# microsmt_pnpboard_v17_sheet_2.net
KiCad netlist of a schematic drawn in Altium Designer
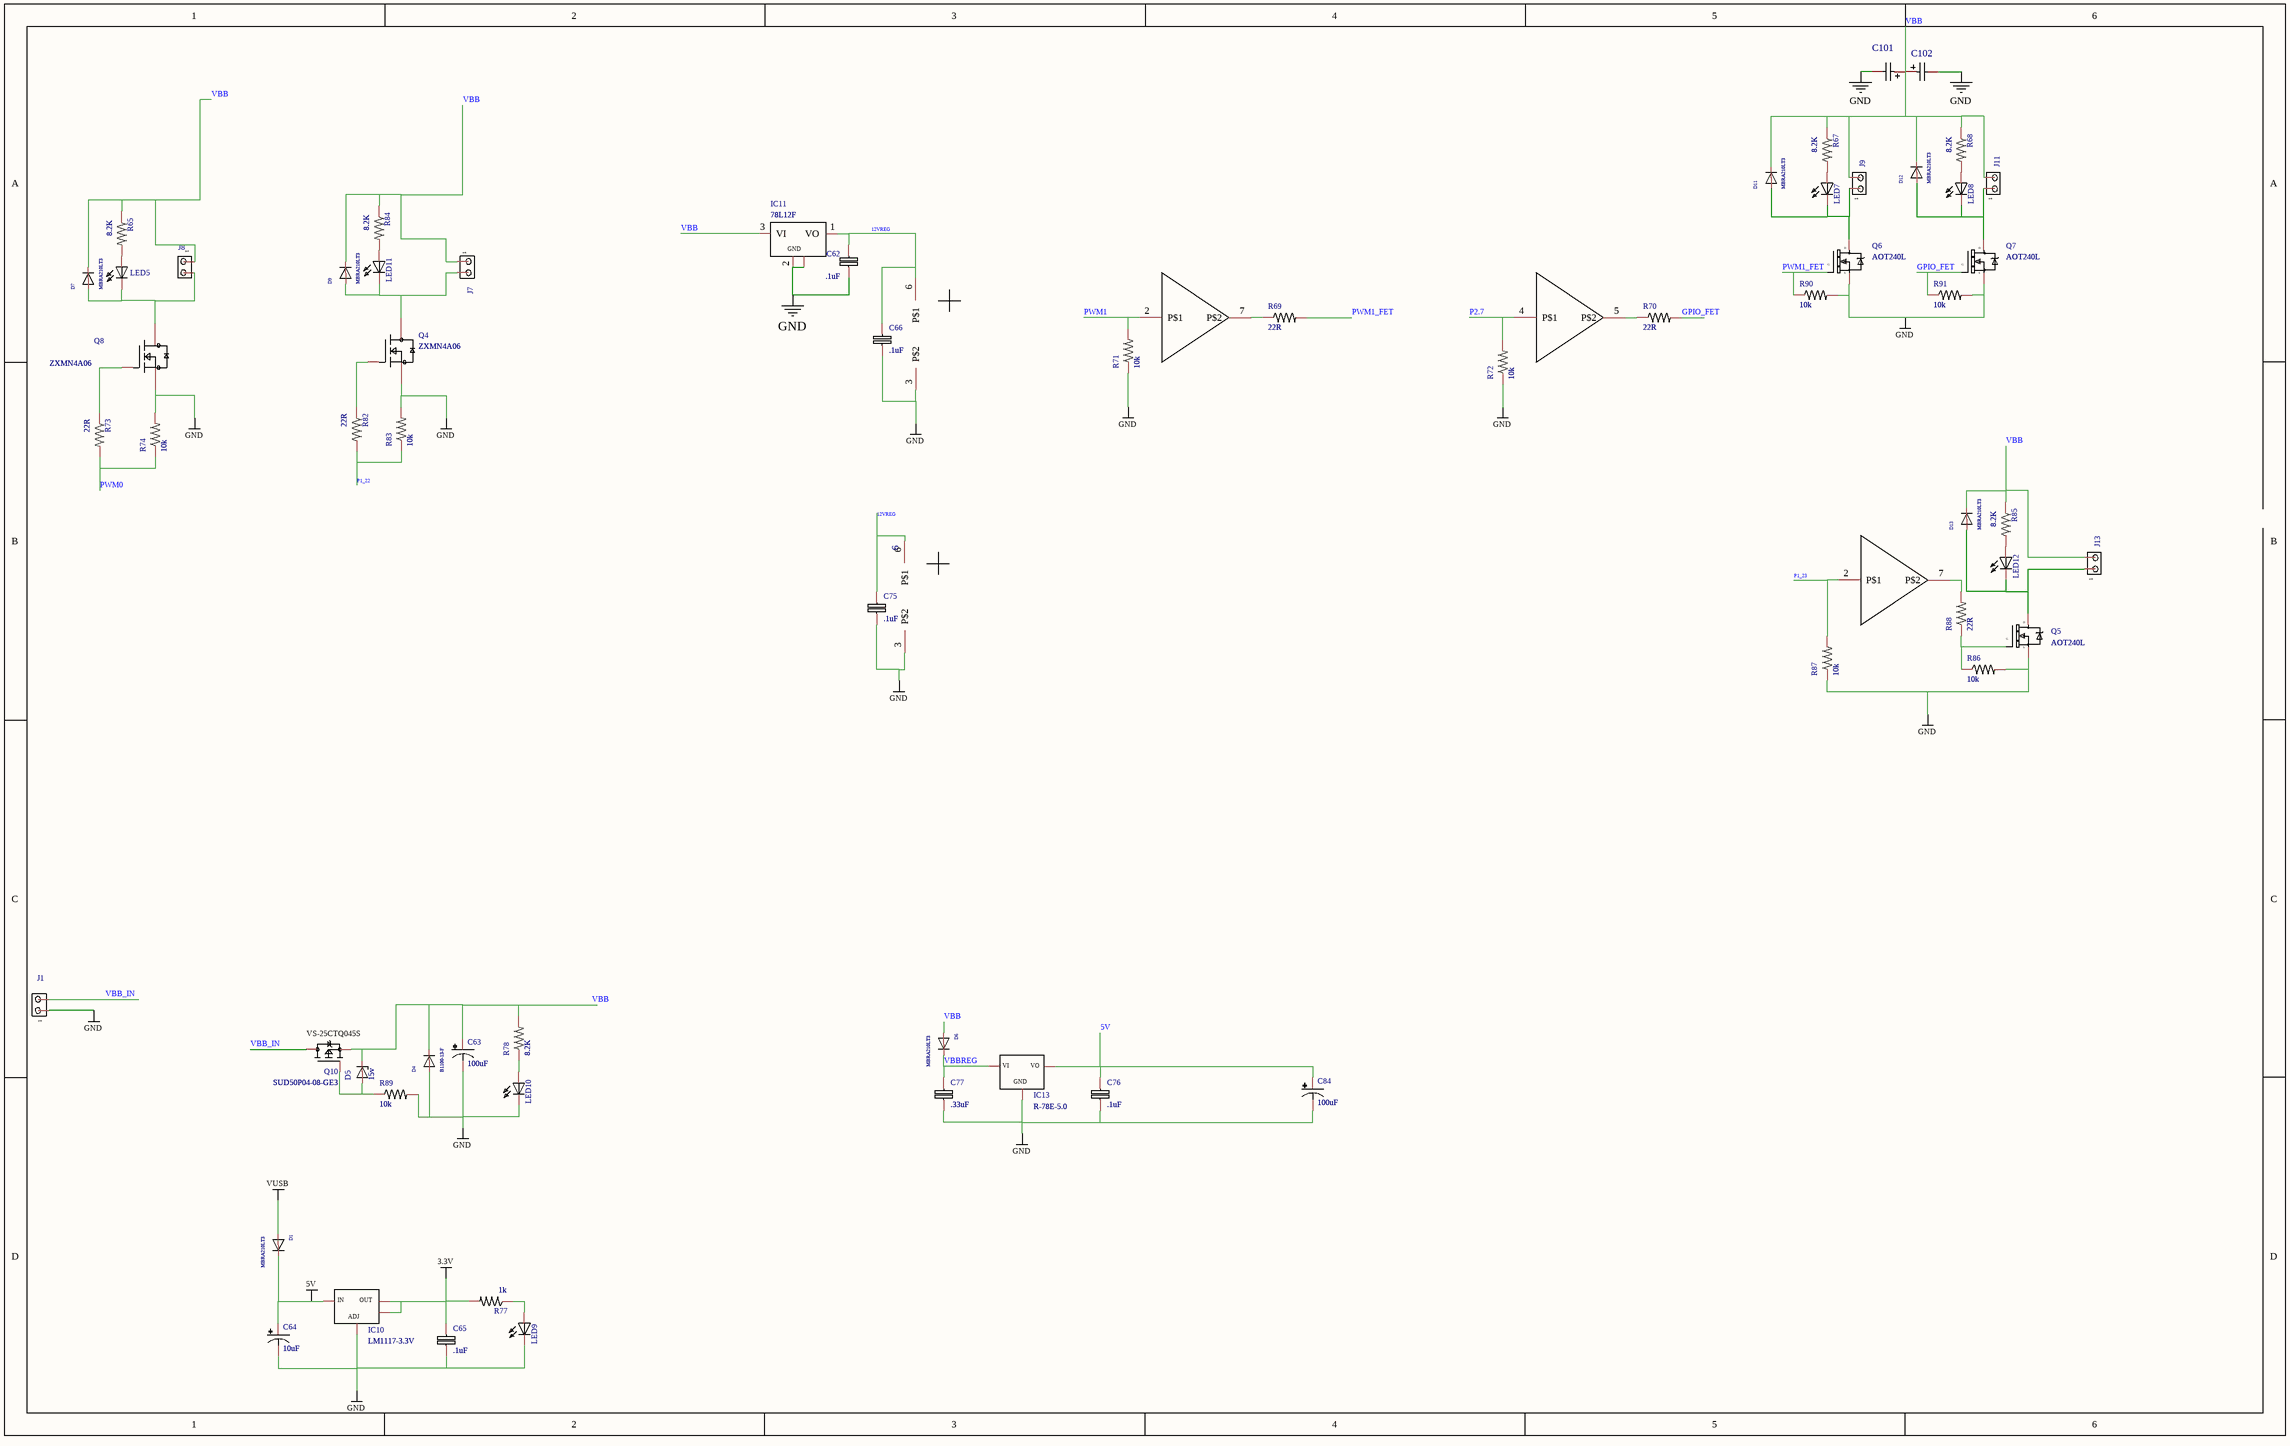
[diagram p0: microsmt_pnpboard_v17_sheet_2.schdoc]

(export (version "E")
  (design (tool "Eeschema 10.0.6"))
  (components
    (comp (ref "C62")
      (value ".1uF")
      (fields (field (name "NAME") ".1uF"))
      (libsource (lib "altium-import") (part "root_0_.1uF_"))
    )
    (comp (ref "C63")
      (value "100uF")
      (fields (field (name "NAME") "100uF"))
      (libsource (lib "") (part "root_0_100uF__1"))
    )
    (comp (ref "C64")
      (value "10uF")
      (fields (field (name "NAME") "10uF"))
      (libsource (lib "altium-import") (part "root_0_10uF_"))
    )
    (comp (ref "C65")
      (value ".1uF")
      (fields (field (name "NAME") ".1uF"))
      (libsource (lib "altium-import") (part "root_0_.1uF_"))
    )
    (comp (ref "C66")
      (value ".1uF")
      (fields (field (name "NAME") ".1uF"))
      (libsource (lib "altium-import") (part "root_0_.1uF_"))
    )
    (comp (ref "C75")
      (value ".1uF")
      (fields (field (name "NAME") ".1uF"))
      (libsource (lib "altium-import") (part "root_0_.1uF_"))
    )
    (comp (ref "C76")
      (value ".1uF")
      (fields (field (name "NAME") ".1uF"))
      (libsource (lib "altium-import") (part "root_0_.1uF_"))
    )
    (comp (ref "C77")
      (value ".33uF")
      (fields (field (name "NAME") ".33uF"))
      (libsource (lib "altium-import") (part "root_0_.33uF_"))
    )
    (comp (ref "C84")
      (value "100uF")
      (fields (field (name "NAME") "100uF"))
      (libsource (lib "altium-import") (part "root_0_100uF_"))
    )
    (comp (ref "C101")
      (value "C_Ele_SMD_3x5.4mm")
      (description "容值:10uF;精度:±20%;额定电压:16V;电容体直径:-;电容体长度:-;纹波电流:-;等效串联电阻:-;工作寿命:2000hrs@85;工作温度:-40~+85;")
      (libsource (lib "altium-import") (part "root_0_C_Ele_SMD_3x5.4mm_"))
    )
    (comp (ref "C102")
      (value "C_Ele_SMD_3x5.4mm")
      (description "容值:10uF;精度:±20%;额定电压:16V;电容体直径:-;电容体长度:-;纹波电流:-;等效串联电阻:-;工作寿命:2000hrs@85;工作温度:-40~+85;")
      (libsource (lib "altium-import") (part "root_2_C_Ele_SMD_3x5.4mm_"))
    )
    (comp (ref "D1")
      (value "MBRA210LT3")
      (fields (field (name "NAME") "MBRA210LT3"))
      (libsource (lib "") (part "root_0_MBRA210LT3__1"))
    )
    (comp (ref "D4")
      (value "B1100-13-F")
      (fields (field (name "NAME") "B1100-13-F"))
      (libsource (lib "altium-import") (part "root_0_B1100-13-F_"))
    )
    (comp (ref "D5")
      (value "15v")
      (fields (field (name "NAME") "15v"))
      (libsource (lib "altium-import") (part "root_0_15v_"))
    )
    (comp (ref "D6")
      (value "MBRA210LT3")
      (fields (field (name "NAME") "MBRA210LT3"))
      (libsource (lib "") (part "root_0_MBRA210LT3__1"))
    )
    (comp (ref "D7")
      (value "MBRA210LT3")
      (fields (field (name "NAME") "MBRA210LT3"))
      (libsource (lib "altium-import") (part "root_0_MBRA210LT3_"))
    )
    (comp (ref "D9")
      (value "MBRA210LT3")
      (fields (field (name "NAME") "MBRA210LT3"))
      (libsource (lib "altium-import") (part "root_0_MBRA210LT3_"))
    )
    (comp (ref "D11")
      (value "MBRA210LT3")
      (fields (field (name "NAME") "MBRA210LT3"))
      (libsource (lib "altium-import") (part "root_0_MBRA210LT3_"))
    )
    (comp (ref "D12")
      (value "MBRA210LT3")
      (fields (field (name "NAME") "MBRA210LT3"))
      (libsource (lib "altium-import") (part "root_0_MBRA210LT3_"))
    )
    (comp (ref "D13")
      (value "MBRA210LT3")
      (fields (field (name "NAME") "MBRA210LT3"))
      (libsource (lib "altium-import") (part "root_0_MBRA210LT3_"))
    )
    (comp (ref "IC10")
      (value "LM1117-3.3V")
      (fields (field (name "NAME") "LM1117-3.3V"))
      (libsource (lib "altium-import") (part "root_0_LM1117-3.3V_"))
    )
    (comp (ref "IC11")
      (value "78L12F")
      (fields (field (name "NAME") "78L12F"))
      (libsource (lib "altium-import") (part "root_0_78L12F_"))
    )
    (comp (ref "IC13")
      (value "R-78E-5.0")
      (fields (field (name "NAME") "R-78E-5.0"))
      (libsource (lib "altium-import") (part "root_0_R-78E-5.0_"))
    )
    (comp (ref "IC14") (value "TC4427") (libsource (lib "altium-import") (part "root_0_TC4427_")))
    (comp (ref "IC15")
      (value "TC4427")
      (fields (field (name "NUMBER") "6"))
      (libsource (lib "") (part "root_0_TC4427__1"))
    )
    (comp (ref "J1") (value "MTA02-100") (libsource (lib "") (part "root_2_MTA02-100__1")))
    (comp (ref "J7") (value "MTA02-100") (libsource (lib "") (part "root_0_MTA02-100__1")))
    (comp (ref "J8") (value "MTA02-100") (libsource (lib "altium-import") (part "root_2_MTA02-100_")))
    (comp (ref "J9") (value "MTA02-100") (libsource (lib "altium-import") (part "root_0_MTA02-100_")))
    (comp (ref "J11") (value "MTA02-100") (libsource (lib "altium-import") (part "root_0_MTA02-100_")))
    (comp (ref "J13") (value "MTA02-100") (libsource (lib "altium-import") (part "root_0_MTA02-100_")))
    (comp (ref "LED5")
      (value "LEDCHIP-LED0805")
      (libsource (lib "altium-import") (part "root_0_LEDCHIP-LED0805_"))
    )
    (comp (ref "LED7")
      (value "LEDCHIP-LED0805")
      (libsource (lib "altium-import") (part "root_0_LEDCHIP-LED0805_"))
    )
    (comp (ref "LED8")
      (value "LEDCHIP-LED0805")
      (libsource (lib "altium-import") (part "root_0_LEDCHIP-LED0805_"))
    )
    (comp (ref "LED9")
      (value "LEDCHIP-LED0805")
      (libsource (lib "altium-import") (part "root_0_LEDCHIP-LED0805_"))
    )
    (comp (ref "LED10")
      (value "LEDCHIP-LED0805")
      (libsource (lib "altium-import") (part "root_0_LEDCHIP-LED0805_"))
    )
    (comp (ref "LED11")
      (value "LEDCHIP-LED0805")
      (libsource (lib "altium-import") (part "root_0_LEDCHIP-LED0805_"))
    )
    (comp (ref "LED12")
      (value "LEDCHIP-LED0805")
      (libsource (lib "altium-import") (part "root_0_LEDCHIP-LED0805_"))
    )
    (comp (ref "Q4")
      (value "ZXMN4A06")
      (fields (field (name "NAME") "ZXMN4A06"))
      (libsource (lib "altium-import") (part "root_0_ZXMN4A06_"))
    )
    (comp (ref "Q5")
      (value "AOT240L")
      (fields (field (name "NAME") "AOT240L"))
      (libsource (lib "") (part "root_0_AOT240L__2"))
    )
    (comp (ref "Q6")
      (value "AOT240L")
      (fields (field (name "NAME") "AOT240L"))
      (libsource (lib "") (part "root_0_AOT240L__1"))
    )
    (comp (ref "Q7")
      (value "AOT240L")
      (fields (field (name "NAME") "AOT240L"))
      (libsource (lib "altium-import") (part "root_0_AOT240L_"))
    )
    (comp (ref "Q8")
      (value "ZXMN4A06")
      (fields (field (name "NAME") "ZXMN4A06"))
      (libsource (lib "") (part "root_0_ZXMN4A06__1"))
    )
    (comp (ref "Q10")
      (value "SUD50P04-08-GE3")
      (fields (field (name "NAME") "SUD50P04-08-GE3"))
      (libsource (lib "altium-import") (part "root_0_SUD50P04-08-GE3_"))
    )
    (comp (ref "R65")
      (value "8.2K")
      (fields (field (name "NAME") "8.2K"))
      (libsource (lib "altium-import") (part "root_0_8.2K_"))
    )
    (comp (ref "R67")
      (value "8.2K")
      (fields (field (name "NAME") "8.2K"))
      (libsource (lib "altium-import") (part "root_0_8.2K_"))
    )
    (comp (ref "R68")
      (value "8.2K")
      (fields (field (name "NAME") "8.2K"))
      (libsource (lib "altium-import") (part "root_0_8.2K_"))
    )
    (comp (ref "R69")
      (value "22R")
      (fields (field (name "NAME") "22R"))
      (libsource (lib "altium-import") (part "root_0_22R_"))
    )
    (comp (ref "R70")
      (value "22R")
      (fields (field (name "NAME") "22R"))
      (libsource (lib "altium-import") (part "root_0_22R_"))
    )
    (comp (ref "R71")
      (value "10k")
      (fields (field (name "NAME") "10k"))
      (libsource (lib "altium-import") (part "root_0_10k_"))
    )
    (comp (ref "R72")
      (value "10k")
      (fields (field (name "NAME") "10k"))
      (libsource (lib "altium-import") (part "root_0_10k_"))
    )
    (comp (ref "R73")
      (value "22R")
      (fields (field (name "NAME") "22R"))
      (libsource (lib "") (part "root_0_22R__1"))
    )
    (comp (ref "R74")
      (value "10k")
      (fields (field (name "NAME") "10k"))
      (libsource (lib "altium-import") (part "root_0_10k_"))
    )
    (comp (ref "R77")
      (value "1k")
      (fields (field (name "NAME") "1k"))
      (libsource (lib "altium-import") (part "root_0_1k_"))
    )
    (comp (ref "R78")
      (value "8.2K")
      (fields (field (name "NAME") "8.2K"))
      (libsource (lib "") (part "root_0_8.2K__1"))
    )
    (comp (ref "R82")
      (value "22R")
      (fields (field (name "NAME") "22R"))
      (libsource (lib "") (part "root_0_22R__1"))
    )
    (comp (ref "R83")
      (value "10k")
      (fields (field (name "NAME") "10k"))
      (libsource (lib "altium-import") (part "root_0_10k_"))
    )
    (comp (ref "R84")
      (value "8.2K")
      (fields (field (name "NAME") "8.2K"))
      (libsource (lib "altium-import") (part "root_0_8.2K_"))
    )
    (comp (ref "R85")
      (value "8.2K")
      (fields (field (name "NAME") "8.2K"))
      (libsource (lib "altium-import") (part "root_0_8.2K_"))
    )
    (comp (ref "R86")
      (value "10k")
      (fields (field (name "NAME") "10k"))
      (libsource (lib "") (part "root_0_10k__1"))
    )
    (comp (ref "R87")
      (value "10k")
      (fields (field (name "NAME") "10k"))
      (libsource (lib "altium-import") (part "root_0_10k_"))
    )
    (comp (ref "R88")
      (value "22R")
      (fields (field (name "NAME") "22R"))
      (libsource (lib "") (part "root_0_22R__2"))
    )
    (comp (ref "R89")
      (value "10k")
      (fields (field (name "NAME") "10k"))
      (libsource (lib "") (part "root_0_10k__1"))
    )
    (comp (ref "R90")
      (value "10k")
      (fields (field (name "NAME") "10k"))
      (libsource (lib "") (part "root_0_10k__1"))
    )
    (comp (ref "R91")
      (value "10k")
      (fields (field (name "NAME") "10k"))
      (libsource (lib "") (part "root_0_10k__1"))
    )
  )
  (nets
    (net (code "1") (name "/12VREG") (class "Default")
      (node (ref "C62") (pin "1") (pinfunction "1_1") (pintype "passive"))
      (node (ref "C66") (pin "1") (pinfunction "1_1") (pintype "passive"))
      (node (ref "C75") (pin "1") (pinfunction "1_1") (pintype "passive"))
      (node (ref "IC11") (pin "1") (pinfunction "VO_1") (pintype "passive"))
      (node (ref "IC14") (pin "6") (pinfunction "P$1_6") (pintype "passive"))
      (node (ref "IC15") (pin "6") (pinfunction "P$1_6") (pintype "passive"))
    )
    (net (code "2") (name "/GPIO_FET") (class "Default")
      (node (ref "Q7") (pin "G") (pinfunction "G_G") (pintype "passive"))
      (node (ref "R70") (pin "2") (pinfunction "2_2") (pintype "passive"))
      (node (ref "R91") (pin "1") (pinfunction "1_1") (pintype "passive"))
    )
    (net (code "3") (name "/P1_22") (class "Default")
      (node (ref "R82") (pin "2") (pinfunction "2_2") (pintype "passive"))
      (node (ref "R83") (pin "1") (pinfunction "1_1") (pintype "passive"))
    )
    (net (code "4") (name "/P1_23") (class "Default")
      (node (ref "IC15") (pin "2") (pinfunction "P$1_2") (pintype "passive"))
      (node (ref "R87") (pin "2") (pinfunction "2_2") (pintype "passive"))
    )
    (net (code "5") (name "/P2.7") (class "Default")
      (node (ref "IC14") (pin "4") (pinfunction "P$1_4") (pintype "passive"))
      (node (ref "R72") (pin "2") (pinfunction "2_2") (pintype "passive"))
    )
    (net (code "6") (name "/PWM0") (class "Default")
      (node (ref "R73") (pin "2") (pinfunction "2_2") (pintype "passive"))
      (node (ref "R74") (pin "1") (pinfunction "1_1") (pintype "passive"))
    )
    (net (code "7") (name "/PWM1") (class "Default")
      (node (ref "IC14") (pin "2") (pinfunction "P$1_2") (pintype "passive"))
      (node (ref "R71") (pin "2") (pinfunction "2_2") (pintype "passive"))
    )
    (net (code "8") (name "/PWM1_FET") (class "Default")
      (node (ref "Q6") (pin "G") (pinfunction "G_G") (pintype "passive"))
      (node (ref "R69") (pin "2") (pinfunction "2_2") (pintype "passive"))
      (node (ref "R90") (pin "1") (pinfunction "1_1") (pintype "passive"))
    )
    (net (code "9") (name "/VBB") (class "Default")
      (node (ref "C101") (pin "1") (pinfunction "1_1") (pintype "passive"))
      (node (ref "C102") (pin "1") (pinfunction "1_1") (pintype "passive"))
      (node (ref "C63") (pin "1") (pinfunction "1_1") (pintype "passive"))
      (node (ref "D11") (pin "C") (pinfunction "C_C") (pintype "passive"))
      (node (ref "D12") (pin "C") (pinfunction "C_C") (pintype "passive"))
      (node (ref "D13") (pin "C") (pinfunction "C_C") (pintype "passive"))
      (node (ref "D4") (pin "C") (pinfunction "C_C") (pintype "passive"))
      (node (ref "D5") (pin "1") (pinfunction "1_1") (pintype "passive"))
      (node (ref "D6") (pin "A") (pinfunction "A_A") (pintype "passive"))
      (node (ref "D7") (pin "C") (pinfunction "C_C") (pintype "passive"))
      (node (ref "D9") (pin "C") (pinfunction "C_C") (pintype "passive"))
      (node (ref "IC11") (pin "3") (pinfunction "VI_3") (pintype "passive"))
      (node (ref "J11") (pin "2") (pinfunction "2_2") (pintype "passive"))
      (node (ref "J13") (pin "2") (pinfunction "2_2") (pintype "passive"))
      (node (ref "J7") (pin "1") (pinfunction "1_1") (pintype "passive"))
      (node (ref "J8") (pin "1") (pinfunction "1_1") (pintype "passive"))
      (node (ref "J9") (pin "2") (pinfunction "2_2") (pintype "passive"))
      (node (ref "Q10") (pin "2") (pinfunction "S_2") (pintype "passive"))
      (node (ref "R65") (pin "1") (pinfunction "1_1") (pintype "passive"))
      (node (ref "R67") (pin "1") (pinfunction "1_1") (pintype "passive"))
      (node (ref "R68") (pin "1") (pinfunction "1_1") (pintype "passive"))
      (node (ref "R78") (pin "2") (pinfunction "2_2") (pintype "passive"))
      (node (ref "R84") (pin "1") (pinfunction "1_1") (pintype "passive"))
      (node (ref "R85") (pin "1") (pinfunction "1_1") (pintype "passive"))
    )
    (net (code "10") (name "/VBBREG") (class "Default")
      (node (ref "C77") (pin "1") (pinfunction "1_1") (pintype "passive"))
      (node (ref "D6") (pin "C") (pinfunction "C_C") (pintype "passive"))
      (node (ref "IC13") (pin "1") (pinfunction "VI_1") (pintype "passive"))
    )
    (net (code "11") (name "/VBB_IN") (class "Default")
      (node (ref "J1") (pin "2") (pinfunction "2_2") (pintype "passive"))
      (node (ref "Q10") (pin "3") (pinfunction "D_3") (pintype "passive"))
    )
    (net (code "12") (name "3.3V") (class "Default")
      (node (ref "C65") (pin "1") (pinfunction "1_1") (pintype "passive"))
      (node (ref "IC10") (pin "2") (pinfunction "OUT_2") (pintype "passive"))
      (node (ref "IC10") (pin "4") (pinfunction "OUT_4") (pintype "passive"))
      (node (ref "R77") (pin "2") (pinfunction "2_2") (pintype "passive"))
    )
    (net (code "13") (name "5V") (class "Default")
      (node (ref "C64") (pin "A") (pinfunction "+_A") (pintype "passive"))
      (node (ref "C76") (pin "1") (pinfunction "1_1") (pintype "passive"))
      (node (ref "C84") (pin "1") (pinfunction "1_1") (pintype "passive"))
      (node (ref "D1") (pin "C") (pinfunction "C_C") (pintype "passive"))
      (node (ref "IC10") (pin "3") (pinfunction "IN_3") (pintype "passive"))
      (node (ref "IC13") (pin "3") (pinfunction "VO_3") (pintype "passive"))
    )
    (net (code "14") (name "GND") (class "Default")
      (node (ref "C101") (pin "2") (pinfunction "2_2") (pintype "passive"))
      (node (ref "C102") (pin "2") (pinfunction "2_2") (pintype "passive"))
      (node (ref "C62") (pin "2") (pinfunction "2_2") (pintype "passive"))
      (node (ref "C63") (pin "2") (pinfunction "2_2") (pintype "passive"))
      (node (ref "C64") (pin "C") (pinfunction "-_C") (pintype "passive"))
      (node (ref "C65") (pin "2") (pinfunction "2_2") (pintype "passive"))
      (node (ref "C66") (pin "2") (pinfunction "2_2") (pintype "passive"))
      (node (ref "C75") (pin "2") (pinfunction "2_2") (pintype "passive"))
      (node (ref "C76") (pin "2") (pinfunction "2_2") (pintype "passive"))
      (node (ref "C77") (pin "2") (pinfunction "2_2") (pintype "passive"))
      (node (ref "C84") (pin "2") (pinfunction "2_2") (pintype "passive"))
      (node (ref "D4") (pin "A") (pinfunction "A_A") (pintype "passive"))
      (node (ref "IC10") (pin "1") (pinfunction "ADJ_1") (pintype "passive"))
      (node (ref "IC11") (pin "2") (pinfunction "GND_2") (pintype "passive"))
      (node (ref "IC13") (pin "2") (pinfunction "GND_2") (pintype "passive"))
      (node (ref "IC14") (pin "3") (pinfunction "P$2_3") (pintype "passive"))
      (node (ref "IC15") (pin "3") (pinfunction "P$2_3") (pintype "passive"))
      (node (ref "J1") (pin "1") (pinfunction "1_1") (pintype "passive"))
      (node (ref "LED10") (pin "1") (pinfunction "1_1") (pintype "passive"))
      (node (ref "LED9") (pin "1") (pinfunction "1_1") (pintype "passive"))
      (node (ref "Q4") (pin "3") (pinfunction "S_3") (pintype "passive"))
      (node (ref "Q5") (pin "S") (pinfunction "S_S") (pintype "passive"))
      (node (ref "Q6") (pin "S") (pinfunction "S_S") (pintype "passive"))
      (node (ref "Q7") (pin "S") (pinfunction "S_S") (pintype "passive"))
      (node (ref "Q8") (pin "3") (pinfunction "S_3") (pintype "passive"))
      (node (ref "R71") (pin "1") (pinfunction "1_1") (pintype "passive"))
      (node (ref "R72") (pin "1") (pinfunction "1_1") (pintype "passive"))
      (node (ref "R74") (pin "2") (pinfunction "2_2") (pintype "passive"))
      (node (ref "R83") (pin "2") (pinfunction "2_2") (pintype "passive"))
      (node (ref "R86") (pin "2") (pinfunction "2_2") (pintype "passive"))
      (node (ref "R87") (pin "1") (pinfunction "1_1") (pintype "passive"))
      (node (ref "R89") (pin "2") (pinfunction "2_2") (pintype "passive"))
      (node (ref "R90") (pin "2") (pinfunction "2_2") (pintype "passive"))
      (node (ref "R91") (pin "2") (pinfunction "2_2") (pintype "passive"))
    )
    (net (code "15") (name "Net-(D11-PadA)") (class "Default")
      (node (ref "D11") (pin "A") (pinfunction "A_A") (pintype "passive"))
      (node (ref "J9") (pin "1") (pinfunction "1_1") (pintype "passive"))
      (node (ref "LED7") (pin "1") (pinfunction "1_1") (pintype "passive"))
      (node (ref "Q6") (pin "D") (pinfunction "D_D") (pintype "passive"))
    )
    (net (code "16") (name "Net-(D12-PadA)") (class "Default")
      (node (ref "D12") (pin "A") (pinfunction "A_A") (pintype "passive"))
      (node (ref "J11") (pin "1") (pinfunction "1_1") (pintype "passive"))
      (node (ref "LED8") (pin "1") (pinfunction "1_1") (pintype "passive"))
      (node (ref "Q7") (pin "D") (pinfunction "D_D") (pintype "passive"))
    )
    (net (code "17") (name "Net-(D13-PadA)") (class "Default")
      (node (ref "D13") (pin "A") (pinfunction "A_A") (pintype "passive"))
      (node (ref "J13") (pin "1") (pinfunction "1_1") (pintype "passive"))
      (node (ref "LED12") (pin "1") (pinfunction "1_1") (pintype "passive"))
      (node (ref "Q5") (pin "D") (pinfunction "D_D") (pintype "passive"))
    )
    (net (code "18") (name "Net-(IC14A-P$2)") (class "Default")
      (node (ref "IC14") (pin "7") (pinfunction "P$2_7") (pintype "passive"))
      (node (ref "R69") (pin "1") (pinfunction "1_1") (pintype "passive"))
    )
    (net (code "19") (name "Net-(IC14B-P$2)") (class "Default")
      (node (ref "IC14") (pin "5") (pinfunction "P$2_5") (pintype "passive"))
      (node (ref "R70") (pin "1") (pinfunction "1_1") (pintype "passive"))
    )
    (net (code "20") (name "Net-(IC15A-P$2)") (class "Default")
      (node (ref "IC15") (pin "7") (pinfunction "P$2_7") (pintype "passive"))
      (node (ref "R88") (pin "2") (pinfunction "2_2") (pintype "passive"))
    )
    (net (code "21") (name "Net-(LED5-Pad2)") (class "Default")
      (node (ref "LED5") (pin "2") (pinfunction "2_2") (pintype "passive"))
      (node (ref "R65") (pin "2") (pinfunction "2_2") (pintype "passive"))
    )
    (net (code "22") (name "Net-(LED7-Pad2)") (class "Default")
      (node (ref "LED7") (pin "2") (pinfunction "2_2") (pintype "passive"))
      (node (ref "R67") (pin "2") (pinfunction "2_2") (pintype "passive"))
    )
    (net (code "23") (name "Net-(LED8-Pad2)") (class "Default")
      (node (ref "LED8") (pin "2") (pinfunction "2_2") (pintype "passive"))
      (node (ref "R68") (pin "2") (pinfunction "2_2") (pintype "passive"))
    )
    (net (code "24") (name "Net-(LED9-Pad2)") (class "Default")
      (node (ref "LED9") (pin "2") (pinfunction "2_2") (pintype "passive"))
      (node (ref "R77") (pin "1") (pinfunction "1_1") (pintype "passive"))
    )
    (net (code "25") (name "Net-(LED10-Pad2)") (class "Default")
      (node (ref "LED10") (pin "2") (pinfunction "2_2") (pintype "passive"))
      (node (ref "R78") (pin "1") (pinfunction "1_1") (pintype "passive"))
    )
    (net (code "26") (name "Net-(LED11-Pad2)") (class "Default")
      (node (ref "LED11") (pin "2") (pinfunction "2_2") (pintype "passive"))
      (node (ref "R84") (pin "2") (pinfunction "2_2") (pintype "passive"))
    )
    (net (code "27") (name "Net-(LED12-Pad2)") (class "Default")
      (node (ref "LED12") (pin "2") (pinfunction "2_2") (pintype "passive"))
      (node (ref "R85") (pin "2") (pinfunction "2_2") (pintype "passive"))
    )
    (net (code "28") (name "Net-(Q4-D)") (class "Default")
      (node (ref "D9") (pin "A") (pinfunction "A_A") (pintype "passive"))
      (node (ref "J7") (pin "2") (pinfunction "2_2") (pintype "passive"))
      (node (ref "LED11") (pin "1") (pinfunction "1_1") (pintype "passive"))
      (node (ref "Q4") (pin "4") (pinfunction "D_4") (pintype "passive"))
    )
    (net (code "29") (name "Net-(Q4-G)") (class "Default")
      (node (ref "Q4") (pin "1") (pinfunction "G_1") (pintype "passive"))
      (node (ref "R82") (pin "1") (pinfunction "1_1") (pintype "passive"))
    )
    (net (code "30") (name "Net-(Q5-PadG)") (class "Default")
      (node (ref "Q5") (pin "G") (pinfunction "G_G") (pintype "passive"))
      (node (ref "R86") (pin "1") (pinfunction "1_1") (pintype "passive"))
      (node (ref "R88") (pin "1") (pinfunction "1_1") (pintype "passive"))
    )
    (net (code "31") (name "Net-(Q8-D)") (class "Default")
      (node (ref "D7") (pin "A") (pinfunction "A_A") (pintype "passive"))
      (node (ref "J8") (pin "2") (pinfunction "2_2") (pintype "passive"))
      (node (ref "LED5") (pin "1") (pinfunction "1_1") (pintype "passive"))
      (node (ref "Q8") (pin "4") (pinfunction "D_4") (pintype "passive"))
    )
    (net (code "32") (name "Net-(Q8-G)") (class "Default")
      (node (ref "Q8") (pin "1") (pinfunction "G_1") (pintype "passive"))
      (node (ref "R73") (pin "1") (pinfunction "1_1") (pintype "passive"))
    )
    (net (code "33") (name "Net-(Q10-G)") (class "Default")
      (node (ref "D5") (pin "2") (pinfunction "2_2") (pintype "passive"))
      (node (ref "Q10") (pin "1") (pinfunction "G_1") (pintype "passive"))
      (node (ref "R89") (pin "1") (pinfunction "1_1") (pintype "passive"))
    )
    (net (code "34") (name "VUSB") (class "Default")
      (node (ref "D1") (pin "A") (pinfunction "A_A") (pintype "passive"))
    )
  )
)
